# MiMo-Button-V2_0.net
KiCad netlist of a schematic drawn in EAGLE
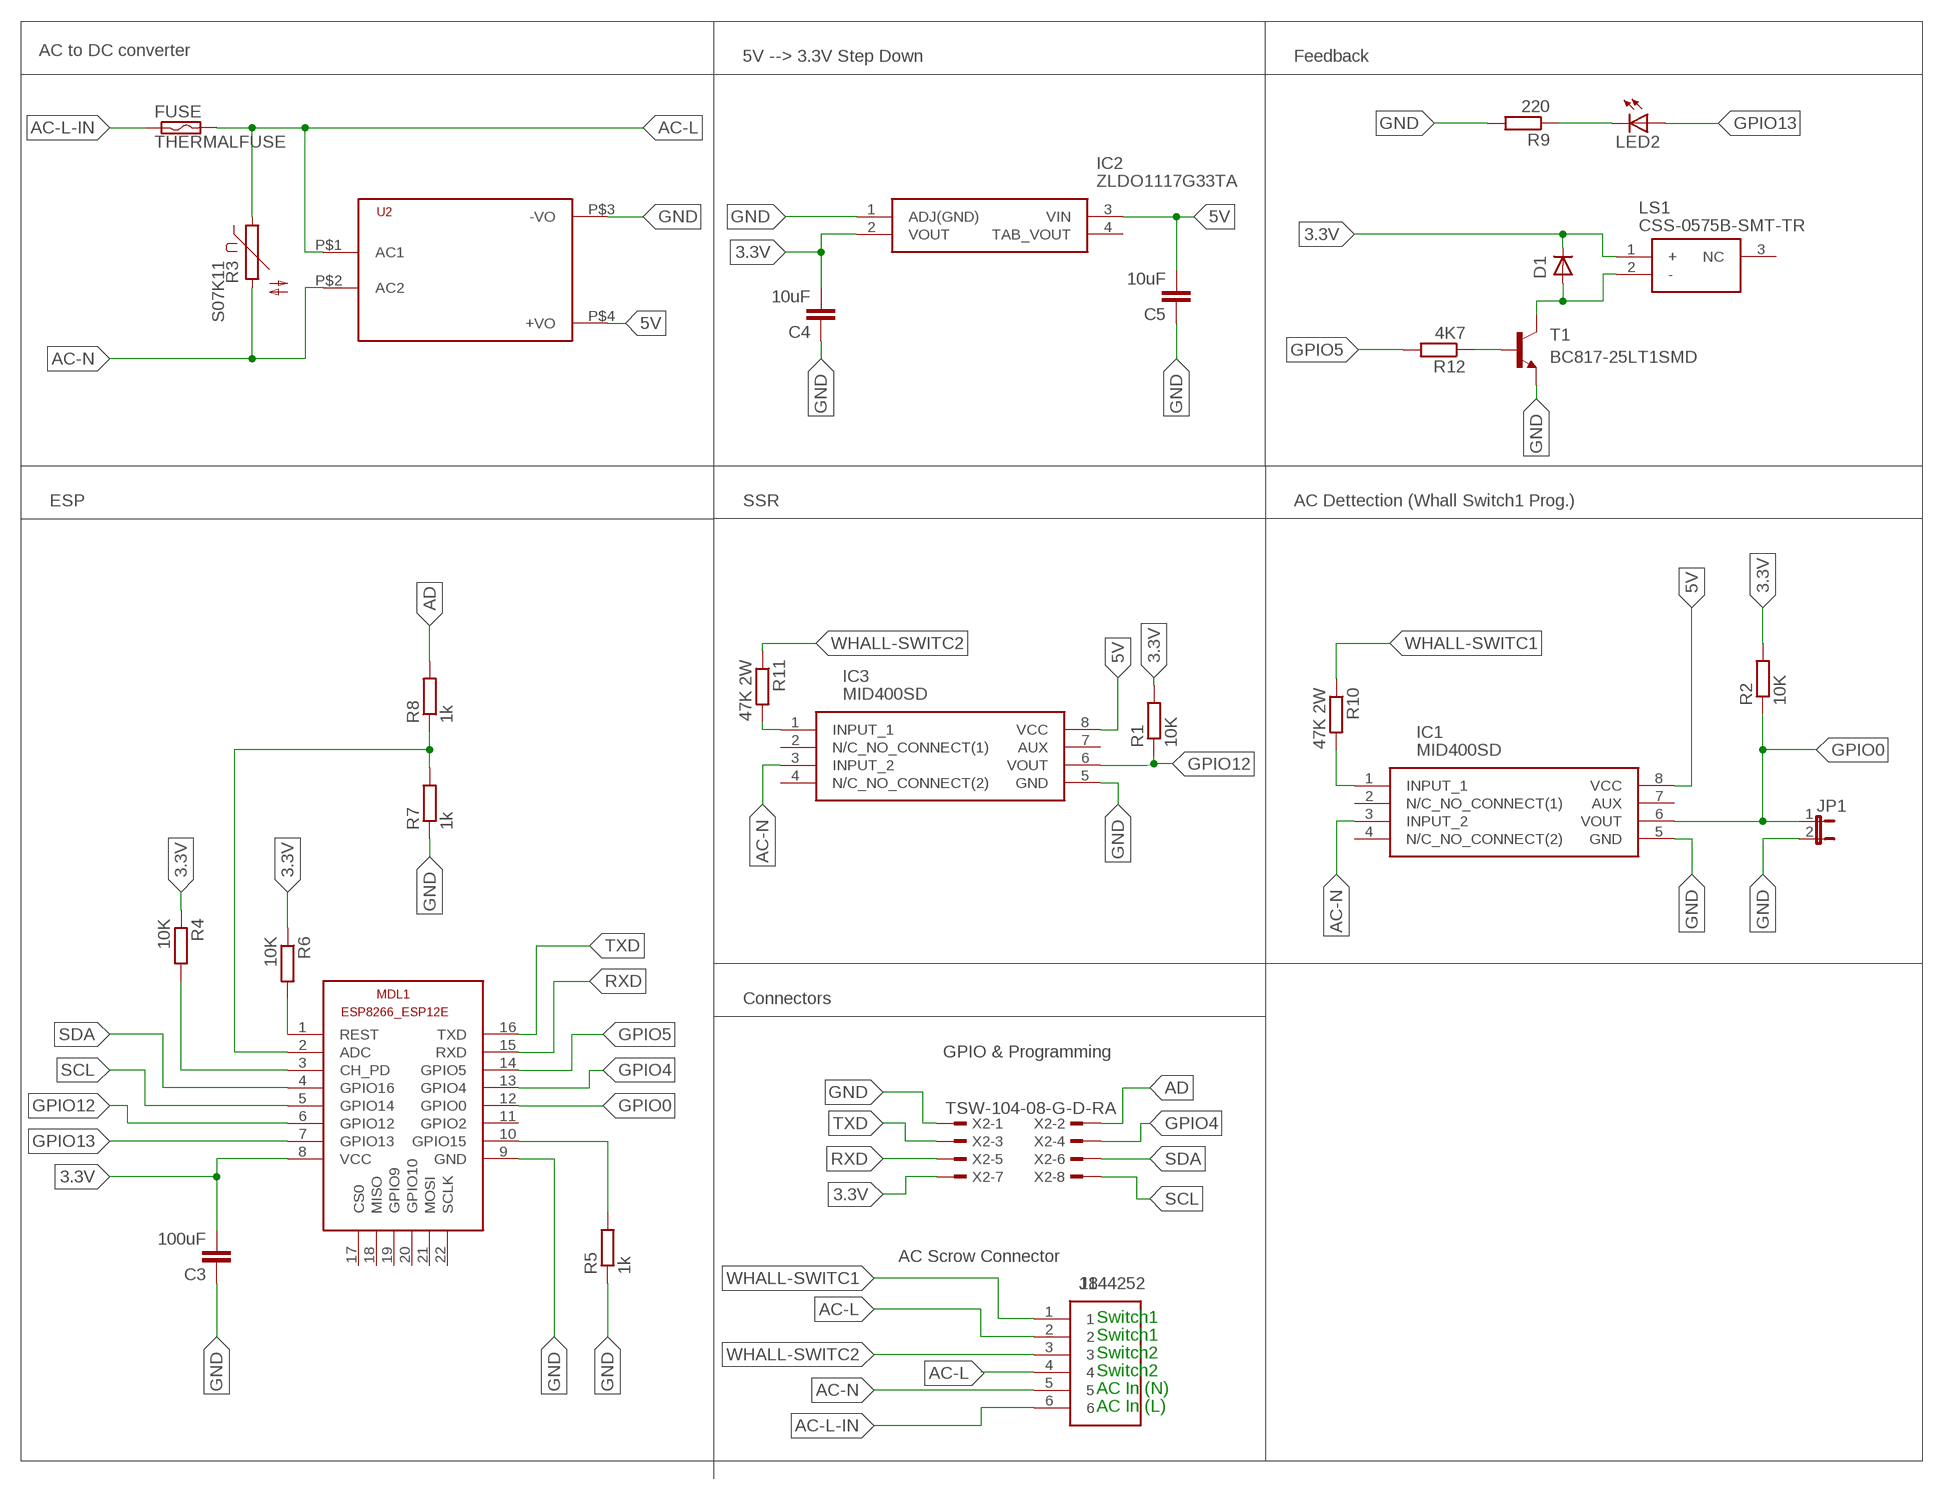
[diagram p0: schematic, sheet 1]

(export (version "E")
  (design (tool "Eeschema 10.0.6"))
  (components
    (comp (ref "C3")
      (value "100uF")
      (footprint "eagle-import:1210")
      (libsource (lib "eagle-import") (part "CAP1210"))
    )
    (comp (ref "C4")
      (value "10uF")
      (footprint "eagle-import:1206")
      (libsource (lib "eagle-import") (part "CAP1206"))
    )
    (comp (ref "C5")
      (value "10uF")
      (footprint "eagle-import:1206")
      (libsource (lib "eagle-import") (part "CAP1206"))
    )
    (comp (ref "D1")
      (value "DIODE-MINIMELF")
      (footprint "eagle-import:MINIMELF")
      (libsource (lib "eagle-import") (part "DIODE-MINIMELF"))
    )
    (comp (ref "FUSE")
      (value "THERMALFUSE")
      (footprint "eagle-import:TE5")
      (libsource (lib "eagle-import") (part "THERMALFUSE12MM"))
    )
    (comp (ref "IC1")
      (value "MID400SD")
      (footprint "eagle-import:SOP254P1030X508-8N")
      (fields (field (name "RS_PART_NUMBER") "8064169P"))
      (libsource (lib "eagle-import") (part "MID400SD"))
    )
    (comp (ref "IC2")
      (value "ZLDO1117G33TA")
      (footprint "eagle-import:SOT230P700X180-4N")
      (fields (field (name "RS_PART_NUMBER") "7515183P"))
      (libsource (lib "eagle-import") (part "ZLDO1117G33TA"))
    )
    (comp (ref "IC3")
      (value "MID400SD")
      (footprint "eagle-import:SOP254P1030X508-8N")
      (fields (field (name "RS_PART_NUMBER") "8064169P"))
      (libsource (lib "eagle-import") (part "MID400SD"))
    )
    (comp (ref "J1")
      (value "1844252")
      (footprint "eagle-import:SHDR6W100P0X350_1X6_2240X920X7")
      (fields (field (name "RS_PART_NUMBER") "8042257"))
      (libsource (lib "eagle-import") (part "1844252"))
    )
    (comp (ref "JP1")
      (value "JP1E")
      (footprint "eagle-import:JP1")
      (libsource (lib "eagle-import") (part "JP1E"))
    )
    (comp (ref "LED2")
      (value "LEDCHIPLED_1206")
      (footprint "eagle-import:CHIPLED_1206")
      (libsource (lib "eagle-import") (part "LEDCHIPLED_1206"))
    )
    (comp (ref "LS1")
      (value "CSS-0575B-SMT-TR")
      (footprint "eagle-import:CSS-0575B-SMT-TR")
      (libsource (lib "eagle-import") (part "CSS-0575B-SMT-TR"))
    )
    (comp (ref "MDL1")
      (value "ESP8266-12EESP8266-ESP12E")
      (footprint "eagle-import:ESP8266-ESP12E")
      (libsource (lib "eagle-import") (part "ESP8266-12EESP8266-ESP12E"))
    )
    (comp (ref "R1")
      (value "10K")
      (footprint "eagle-import:R1206")
      (libsource (lib "eagle-import") (part "RR1206"))
    )
    (comp (ref "R2")
      (value "10K")
      (footprint "eagle-import:R1206")
      (libsource (lib "eagle-import") (part "RR1206"))
    )
    (comp (ref "R3")
      (value "S07K11")
      (footprint "eagle-import:S07K11")
      (libsource (lib "eagle-import") (part "S07K11"))
    )
    (comp (ref "R4")
      (value "10K")
      (footprint "eagle-import:R1206")
      (libsource (lib "eagle-import") (part "RR1206"))
    )
    (comp (ref "R5")
      (value "1k")
      (footprint "eagle-import:R1206")
      (libsource (lib "eagle-import") (part "RR1206"))
    )
    (comp (ref "R6")
      (value "10K")
      (footprint "eagle-import:R1206")
      (libsource (lib "eagle-import") (part "RR1206"))
    )
    (comp (ref "R7")
      (value "1k")
      (footprint "eagle-import:R1206")
      (libsource (lib "eagle-import") (part "RR1206"))
    )
    (comp (ref "R8")
      (value "1k")
      (footprint "eagle-import:R1206")
      (libsource (lib "eagle-import") (part "RR1206"))
    )
    (comp (ref "R9")
      (value "220")
      (footprint "eagle-import:R1206")
      (libsource (lib "eagle-import") (part "RR1206"))
    )
    (comp (ref "R10")
      (value "47K 2W")
      (footprint "eagle-import:R2512")
      (libsource (lib "eagle-import") (part "RR2512"))
    )
    (comp (ref "R11")
      (value "47K 2W")
      (footprint "eagle-import:R2512")
      (libsource (lib "eagle-import") (part "RR2512"))
    )
    (comp (ref "R12")
      (value "4K7")
      (footprint "eagle-import:R1206")
      (libsource (lib "eagle-import") (part "RR1206"))
    )
    (comp (ref "T1")
      (value "BC817-25LT1SMD")
      (footprint "eagle-import:SOT23-BEC")
      (libsource (lib "eagle-import") (part "BC817SMD-25LT1"))
    )
    (comp (ref "U2")
      (value "HLK-PM013W")
      (footprint "eagle-import:HLK-PM01")
      (libsource (lib "eagle-import") (part "HLK-PM013W"))
    )
    (comp (ref "X2")
      (value "TSW-104-08-G-D-RA")
      (footprint "eagle-import:TSW-104-08-G-D-RA")
      (fields (field (name "MF") "Samtec Inc."))
      (libsource (lib "eagle-import") (part "TSW-104--G-D-RA08"))
    )
  )
  (nets
    (net (code "1") (name "3.3V") (class "Default")
      (node (ref "C3") (pin "2") (pinfunction "2_2") (pintype "passive"))
      (node (ref "C4") (pin "2") (pinfunction "2_2") (pintype "passive"))
      (node (ref "D1") (pin "C") (pinfunction "C_C") (pintype "passive"))
      (node (ref "IC2") (pin "2") (pinfunction "VOUT_2") (pintype "output"))
      (node (ref "LS1") (pin "1") (pinfunction "+_1") (pintype "input"))
      (node (ref "MDL1") (pin "8") (pinfunction "VCC_8") (pintype "bidirectional"))
      (node (ref "R1") (pin "2") (pinfunction "2_2") (pintype "passive"))
      (node (ref "R2") (pin "2") (pinfunction "2_2") (pintype "passive"))
      (node (ref "R4") (pin "1") (pinfunction "1_1") (pintype "passive"))
      (node (ref "R6") (pin "1") (pinfunction "1_1") (pintype "passive"))
      (node (ref "X2") (pin "7") (pinfunction "1_7") (pintype "passive"))
    )
    (net (code "2") (name "5V") (class "Default")
      (node (ref "C5") (pin "2") (pinfunction "2_2") (pintype "passive"))
      (node (ref "IC1") (pin "8") (pinfunction "VCC_8") (pintype "input"))
      (node (ref "IC2") (pin "3") (pinfunction "VIN_3") (pintype "input"))
      (node (ref "IC3") (pin "8") (pinfunction "VCC_8") (pintype "input"))
      (node (ref "U2") (pin "P$4") (pinfunction "+VO_P$4") (pintype "bidirectional"))
    )
    (net (code "3") (name "AC-L") (class "Default")
      (node (ref "FUSE") (pin "2") (pinfunction "2_2") (pintype "passive"))
      (node (ref "J1") (pin "2") (pinfunction "2_2") (pintype "bidirectional"))
      (node (ref "J1") (pin "4") (pinfunction "4_4") (pintype "bidirectional"))
      (node (ref "R3") (pin "1") (pinfunction "1_1") (pintype "passive"))
      (node (ref "U2") (pin "P$1") (pinfunction "AC1_P$1") (pintype "bidirectional"))
    )
    (net (code "4") (name "AC-L-IN") (class "Default")
      (node (ref "FUSE") (pin "1") (pinfunction "1_1") (pintype "passive"))
      (node (ref "J1") (pin "6") (pinfunction "6_6") (pintype "bidirectional"))
    )
    (net (code "5") (name "AC-N") (class "Default")
      (node (ref "IC1") (pin "3") (pinfunction "INPUT_2_3") (pintype "input"))
      (node (ref "IC3") (pin "3") (pinfunction "INPUT_2_3") (pintype "input"))
      (node (ref "J1") (pin "5") (pinfunction "5_5") (pintype "bidirectional"))
      (node (ref "R3") (pin "2") (pinfunction "2_2") (pintype "passive"))
      (node (ref "U2") (pin "P$2") (pinfunction "AC2_P$2") (pintype "bidirectional"))
    )
    (net (code "6") (name "AD") (class "Default")
      (node (ref "R8") (pin "2") (pinfunction "2_2") (pintype "passive"))
      (node (ref "X2") (pin "2") (pinfunction "1_2") (pintype "passive"))
    )
    (net (code "7") (name "GND") (class "Default")
      (node (ref "C3") (pin "1") (pinfunction "1_1") (pintype "passive"))
      (node (ref "C4") (pin "1") (pinfunction "1_1") (pintype "passive"))
      (node (ref "C5") (pin "1") (pinfunction "1_1") (pintype "passive"))
      (node (ref "IC1") (pin "5") (pinfunction "GND_5") (pintype "input"))
      (node (ref "IC2") (pin "1") (pinfunction "ADJ(GND)_1") (pintype "power_in"))
      (node (ref "IC3") (pin "5") (pinfunction "GND_5") (pintype "input"))
      (node (ref "JP1") (pin "2") (pinfunction "2_2") (pintype "passive"))
      (node (ref "MDL1") (pin "9") (pinfunction "GND_9") (pintype "bidirectional"))
      (node (ref "R5") (pin "1") (pinfunction "1_1") (pintype "passive"))
      (node (ref "R7") (pin "1") (pinfunction "1_1") (pintype "passive"))
      (node (ref "R9") (pin "2") (pinfunction "2_2") (pintype "passive"))
      (node (ref "T1") (pin "E") (pinfunction "E_E") (pintype "passive"))
      (node (ref "U2") (pin "P$3") (pinfunction "-VO_P$3") (pintype "bidirectional"))
      (node (ref "X2") (pin "1") (pinfunction "1_1") (pintype "passive"))
    )
    (net (code "8") (name "GPIO0") (class "Default")
      (node (ref "IC1") (pin "6") (pinfunction "VOUT_6") (pintype "input"))
      (node (ref "JP1") (pin "1") (pinfunction "1_1") (pintype "passive"))
      (node (ref "MDL1") (pin "12") (pinfunction "GPIO0_12") (pintype "bidirectional"))
      (node (ref "R2") (pin "1") (pinfunction "1_1") (pintype "passive"))
    )
    (net (code "9") (name "GPIO4") (class "Default")
      (node (ref "MDL1") (pin "13") (pinfunction "GPIO4_13") (pintype "bidirectional"))
      (node (ref "X2") (pin "4") (pinfunction "1_4") (pintype "passive"))
    )
    (net (code "10") (name "GPIO5") (class "Default")
      (node (ref "MDL1") (pin "14") (pinfunction "GPIO5_14") (pintype "bidirectional"))
      (node (ref "R12") (pin "2") (pinfunction "2_2") (pintype "passive"))
    )
    (net (code "11") (name "GPIO12") (class "Default")
      (node (ref "IC3") (pin "6") (pinfunction "VOUT_6") (pintype "input"))
      (node (ref "MDL1") (pin "6") (pinfunction "GPIO12_6") (pintype "bidirectional"))
      (node (ref "R1") (pin "1") (pinfunction "1_1") (pintype "passive"))
    )
    (net (code "12") (name "GPIO13") (class "Default")
      (node (ref "LED2") (pin "A") (pinfunction "A_A") (pintype "passive"))
      (node (ref "MDL1") (pin "7") (pinfunction "GPIO13_7") (pintype "bidirectional"))
    )
    (net (code "13") (name "Net-(IC1-INPUT_1)") (class "Default")
      (node (ref "IC1") (pin "1") (pinfunction "INPUT_1_1") (pintype "input"))
      (node (ref "R10") (pin "2") (pinfunction "2_2") (pintype "passive"))
    )
    (net (code "14") (name "Net-(IC3-INPUT_1)") (class "Default")
      (node (ref "IC3") (pin "1") (pinfunction "INPUT_1_1") (pintype "input"))
      (node (ref "R11") (pin "2") (pinfunction "2_2") (pintype "passive"))
    )
    (net (code "15") (name "Net-(LED2-PadC)") (class "Default")
      (node (ref "LED2") (pin "C") (pinfunction "C_C") (pintype "passive"))
      (node (ref "R9") (pin "1") (pinfunction "1_1") (pintype "passive"))
    )
    (net (code "16") (name "Net-(LS1--)") (class "Default")
      (node (ref "D1") (pin "A") (pinfunction "A_A") (pintype "passive"))
      (node (ref "LS1") (pin "2") (pinfunction "-_2") (pintype "input"))
      (node (ref "T1") (pin "C") (pinfunction "C_C") (pintype "passive"))
    )
    (net (code "17") (name "Net-(MDL1-ADC)") (class "Default")
      (node (ref "MDL1") (pin "2") (pinfunction "ADC_2") (pintype "bidirectional"))
      (node (ref "R7") (pin "2") (pinfunction "2_2") (pintype "passive"))
      (node (ref "R8") (pin "1") (pinfunction "1_1") (pintype "passive"))
    )
    (net (code "18") (name "Net-(MDL1-CH_PD)") (class "Default")
      (node (ref "MDL1") (pin "3") (pinfunction "CH_PD_3") (pintype "bidirectional"))
      (node (ref "R4") (pin "2") (pinfunction "2_2") (pintype "passive"))
    )
    (net (code "19") (name "Net-(MDL1-GPIO15)") (class "Default")
      (node (ref "MDL1") (pin "10") (pinfunction "GPIO15_10") (pintype "bidirectional"))
      (node (ref "R5") (pin "2") (pinfunction "2_2") (pintype "passive"))
    )
    (net (code "20") (name "Net-(MDL1-REST)") (class "Default")
      (node (ref "MDL1") (pin "1") (pinfunction "REST_1") (pintype "bidirectional"))
      (node (ref "R6") (pin "2") (pinfunction "2_2") (pintype "passive"))
    )
    (net (code "21") (name "Net-(R12-Pad1)") (class "Default")
      (node (ref "R12") (pin "1") (pinfunction "1_1") (pintype "passive"))
      (node (ref "T1") (pin "B") (pinfunction "B_B") (pintype "passive"))
    )
    (net (code "22") (name "RXD") (class "Default")
      (node (ref "MDL1") (pin "15") (pinfunction "RXD_15") (pintype "bidirectional"))
      (node (ref "X2") (pin "5") (pinfunction "1_5") (pintype "passive"))
    )
    (net (code "23") (name "SCL") (class "Default")
      (node (ref "MDL1") (pin "5") (pinfunction "GPIO14_5") (pintype "bidirectional"))
      (node (ref "X2") (pin "8") (pinfunction "1_8") (pintype "passive"))
    )
    (net (code "24") (name "SDA") (class "Default")
      (node (ref "MDL1") (pin "4") (pinfunction "GPIO16_4") (pintype "bidirectional"))
      (node (ref "X2") (pin "6") (pinfunction "1_6") (pintype "passive"))
    )
    (net (code "25") (name "TXD") (class "Default")
      (node (ref "MDL1") (pin "16") (pinfunction "TXD_16") (pintype "bidirectional"))
      (node (ref "X2") (pin "3") (pinfunction "1_3") (pintype "passive"))
    )
    (net (code "26") (name "WHALL-SWITC1") (class "Default")
      (node (ref "J1") (pin "1") (pinfunction "1_1") (pintype "bidirectional"))
      (node (ref "R10") (pin "1") (pinfunction "1_1") (pintype "passive"))
    )
    (net (code "27") (name "WHALL-SWITC2") (class "Default")
      (node (ref "J1") (pin "3") (pinfunction "3_3") (pintype "bidirectional"))
      (node (ref "R11") (pin "1") (pinfunction "1_1") (pintype "passive"))
    )
    (net (code "28") (name "unconnected-(IC1-AUX-Pad7)") (class "Default")
      (node (ref "IC1") (pin "7") (pinfunction "AUX_7") (pintype "input"))
    )
    (net (code "29") (name "unconnected-(IC1-N{slash}C_NO_CONNECT(1)-Pad2)") (class "Default")
      (node (ref "IC1") (pin "2") (pinfunction "N/C_NO_CONNECT(1)_2") (pintype "input"))
    )
    (net (code "30") (name "unconnected-(IC1-N{slash}C_NO_CONNECT(2)-Pad4)") (class "Default")
      (node (ref "IC1") (pin "4") (pinfunction "N/C_NO_CONNECT(2)_4") (pintype "input"))
    )
    (net (code "31") (name "unconnected-(IC2-TAB_VOUT-Pad4)") (class "Default")
      (node (ref "IC2") (pin "4") (pinfunction "TAB_VOUT_4") (pintype "output"))
    )
    (net (code "32") (name "unconnected-(IC3-AUX-Pad7)") (class "Default")
      (node (ref "IC3") (pin "7") (pinfunction "AUX_7") (pintype "input"))
    )
    (net (code "33") (name "unconnected-(IC3-N{slash}C_NO_CONNECT(1)-Pad2)") (class "Default")
      (node (ref "IC3") (pin "2") (pinfunction "N/C_NO_CONNECT(1)_2") (pintype "input"))
    )
    (net (code "34") (name "unconnected-(IC3-N{slash}C_NO_CONNECT(2)-Pad4)") (class "Default")
      (node (ref "IC3") (pin "4") (pinfunction "N/C_NO_CONNECT(2)_4") (pintype "input"))
    )
    (net (code "35") (name "unconnected-(LS1-NC-Pad3)") (class "Default")
      (node (ref "LS1") (pin "3") (pinfunction "NC_3") (pintype "input"))
    )
    (net (code "36") (name "unconnected-(MDL1-CS0-Pad17)") (class "Default")
      (node (ref "MDL1") (pin "17") (pinfunction "CS0_17") (pintype "bidirectional"))
    )
    (net (code "37") (name "unconnected-(MDL1-GPIO2-Pad11)") (class "Default")
      (node (ref "MDL1") (pin "11") (pinfunction "GPIO2_11") (pintype "bidirectional"))
    )
    (net (code "38") (name "unconnected-(MDL1-GPIO9-Pad19)") (class "Default")
      (node (ref "MDL1") (pin "19") (pinfunction "GPIO9_19") (pintype "bidirectional"))
    )
    (net (code "39") (name "unconnected-(MDL1-GPIO10-Pad20)") (class "Default")
      (node (ref "MDL1") (pin "20") (pinfunction "GPIO10_20") (pintype "bidirectional"))
    )
    (net (code "40") (name "unconnected-(MDL1-MISO-Pad18)") (class "Default")
      (node (ref "MDL1") (pin "18") (pinfunction "MISO_18") (pintype "bidirectional"))
    )
    (net (code "41") (name "unconnected-(MDL1-MOSI-Pad21)") (class "Default")
      (node (ref "MDL1") (pin "21") (pinfunction "MOSI_21") (pintype "bidirectional"))
    )
    (net (code "42") (name "unconnected-(MDL1-SCLK-Pad22)") (class "Default")
      (node (ref "MDL1") (pin "22") (pinfunction "SCLK_22") (pintype "bidirectional"))
    )
  )
)
